# SCH_Adamjames_2023-03-12.net
KiCad netlist of a schematic drawn in EasyEDA
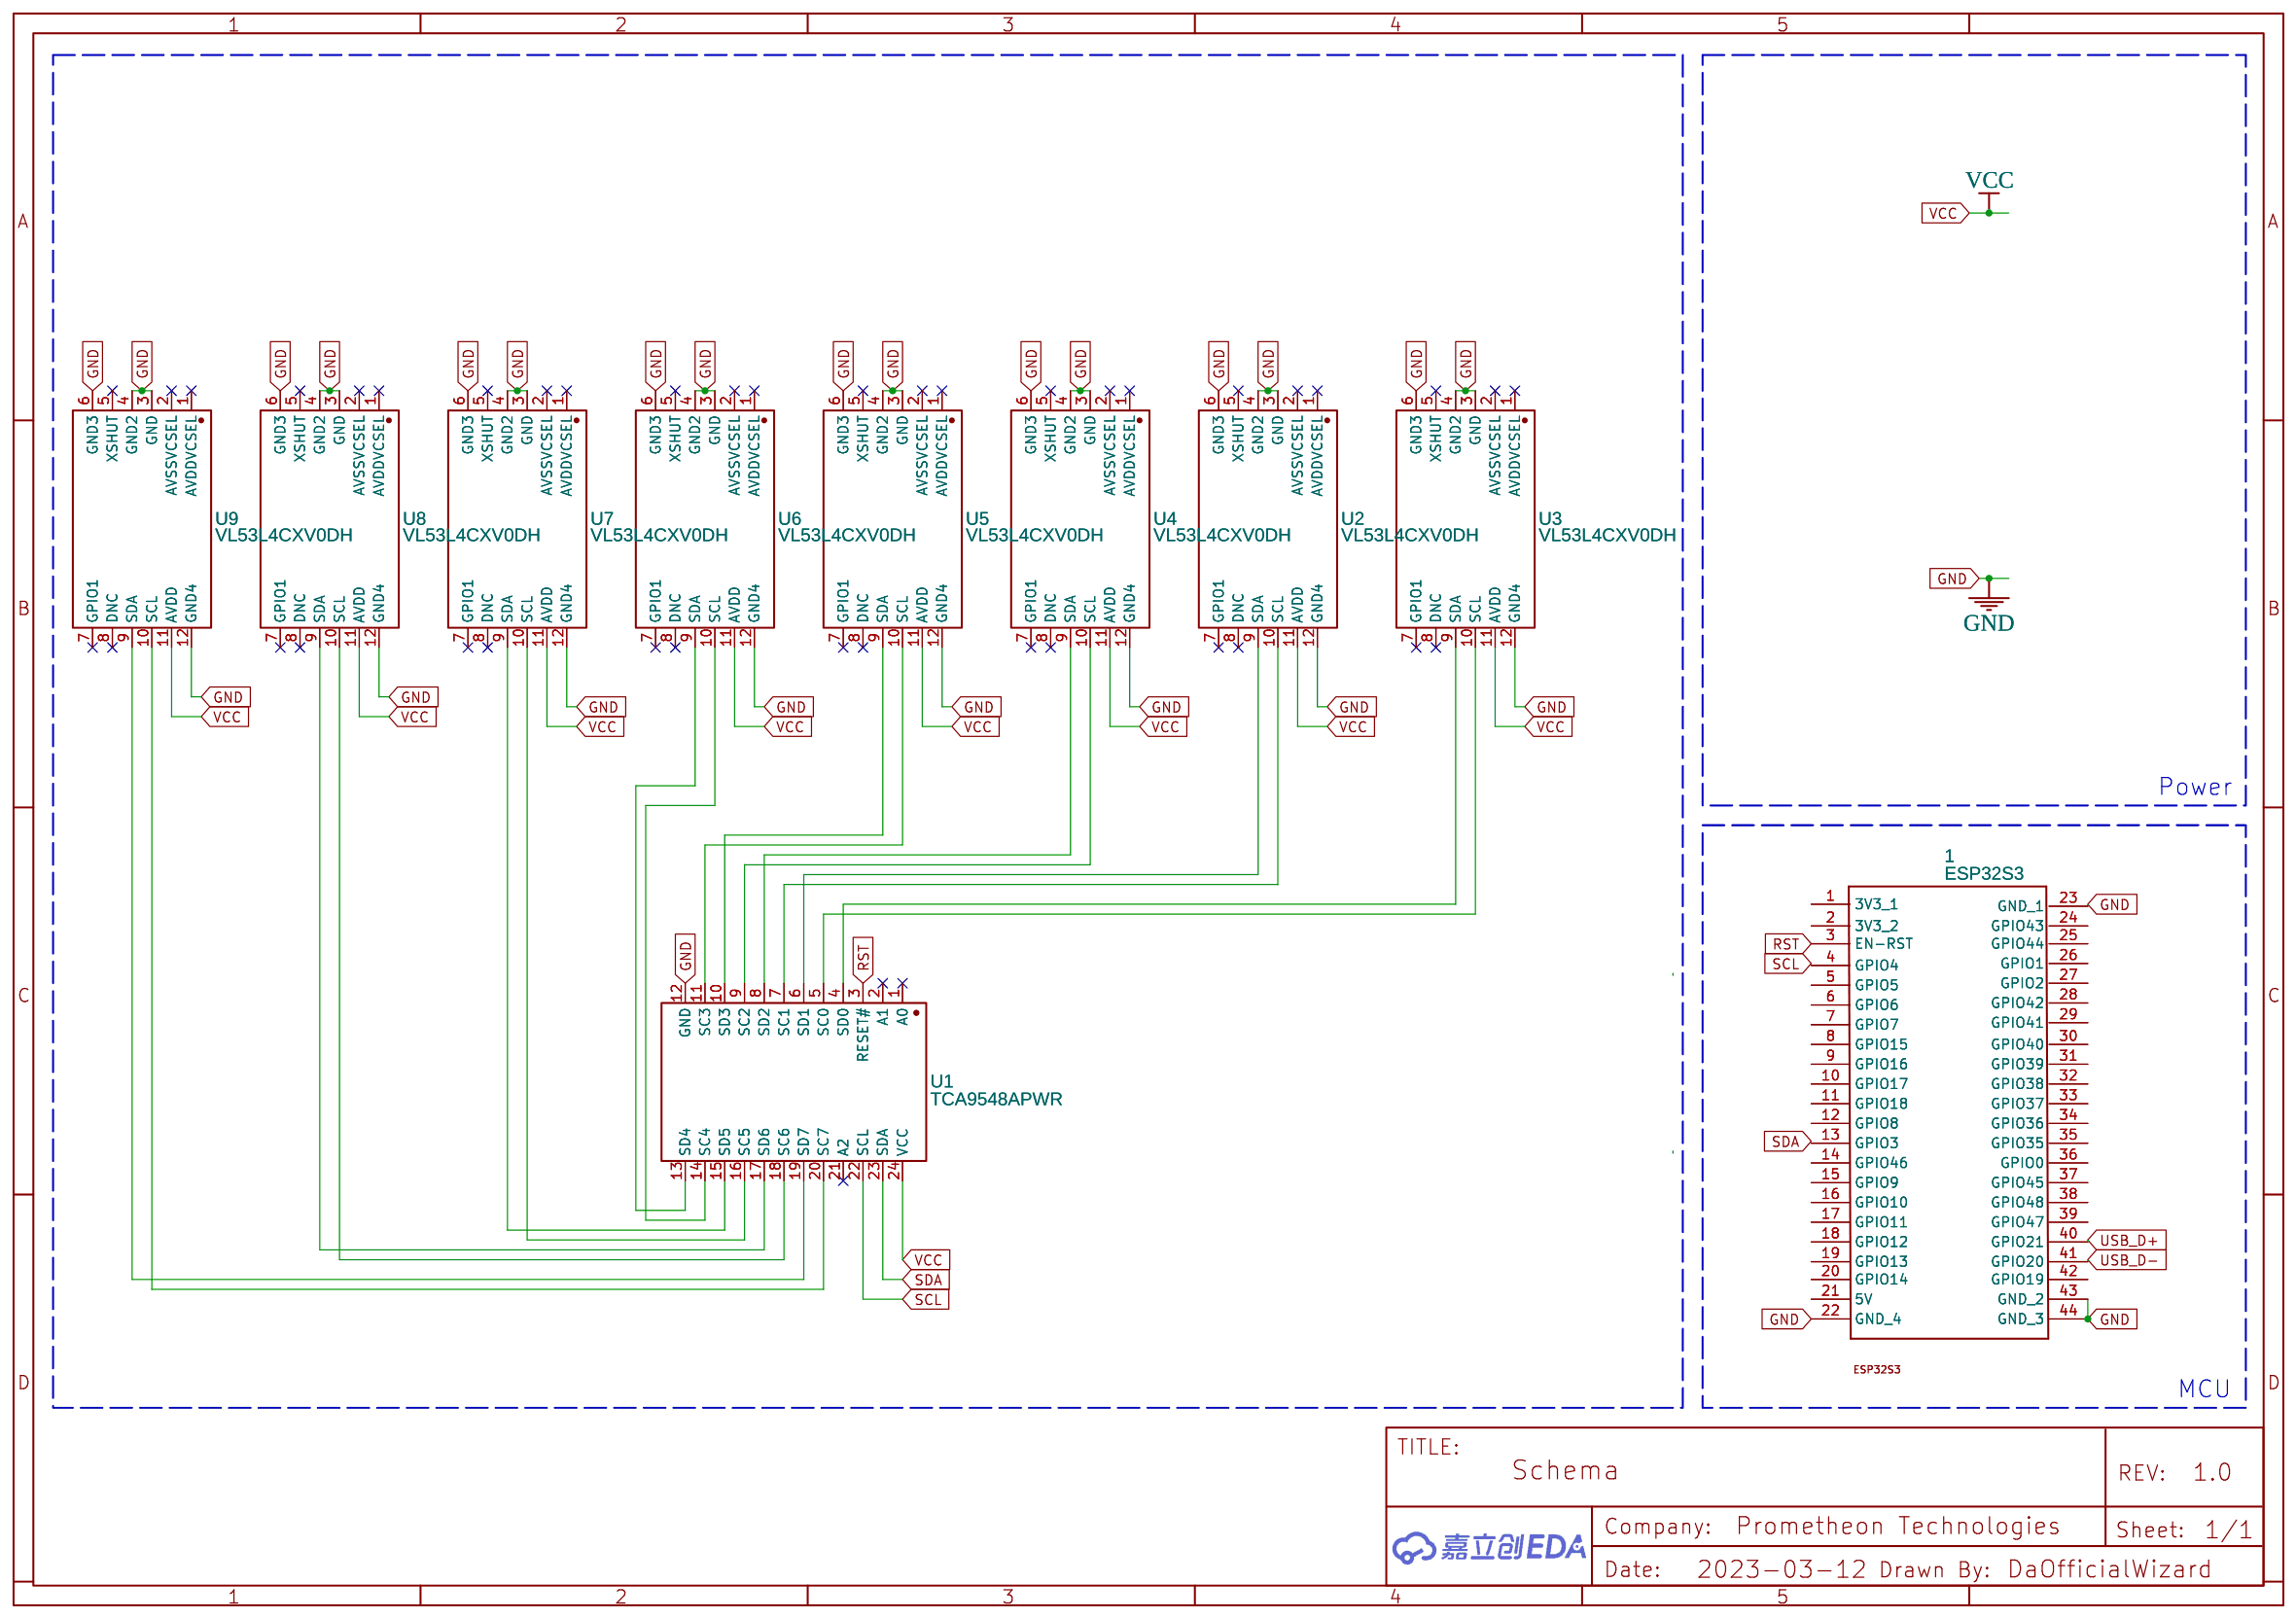
[diagram p0: schematic sheet]

(export (version "E")
  (design (tool "Eeschema 10.0.6"))
  (components
    (comp (ref "1") (value "ESP32S3") (libsource (lib "") (part "ESP32S3")))
    (comp (ref "U1")
      (value "TCA9548APWR")
      (fields (field (name "BOM_Supplier Part") "C130026"))
      (libsource (lib "") (part "TCA9548APWR"))
    )
    (comp (ref "U2")
      (value "VL53L4CXV0DH")
      (fields (field (name "BOM_Manufacturer Part") "VL53L0X") (field (name "BOM_Supplier Part") "C2929940"))
      (libsource (lib "") (part "VL53L4CXV0DH"))
    )
    (comp (ref "U3")
      (value "VL53L4CXV0DH")
      (fields (field (name "BOM_Manufacturer Part") "VL53L0X") (field (name "BOM_Supplier Part") "C2929940"))
      (libsource (lib "") (part "VL53L4CXV0DH"))
    )
    (comp (ref "U4")
      (value "VL53L4CXV0DH")
      (fields (field (name "BOM_Manufacturer Part") "VL53L0X") (field (name "BOM_Supplier Part") "C2929940"))
      (libsource (lib "") (part "VL53L4CXV0DH"))
    )
    (comp (ref "U5")
      (value "VL53L4CXV0DH")
      (fields (field (name "BOM_Manufacturer Part") "VL53L0X") (field (name "BOM_Supplier Part") "C2929940"))
      (libsource (lib "") (part "VL53L4CXV0DH"))
    )
    (comp (ref "U6")
      (value "VL53L4CXV0DH")
      (fields (field (name "BOM_Manufacturer Part") "VL53L0X") (field (name "BOM_Supplier Part") "C2929940"))
      (libsource (lib "") (part "VL53L4CXV0DH"))
    )
    (comp (ref "U7")
      (value "VL53L4CXV0DH")
      (fields (field (name "BOM_Manufacturer Part") "VL53L0X") (field (name "BOM_Supplier Part") "C2929940"))
      (libsource (lib "") (part "VL53L4CXV0DH"))
    )
    (comp (ref "U8")
      (value "VL53L4CXV0DH")
      (fields (field (name "BOM_Manufacturer Part") "VL53L0X") (field (name "BOM_Supplier Part") "C2929940"))
      (libsource (lib "") (part "VL53L4CXV0DH"))
    )
    (comp (ref "U9")
      (value "VL53L4CXV0DH")
      (fields (field (name "BOM_Manufacturer Part") "VL53L0X") (field (name "BOM_Supplier Part") "C2929940"))
      (libsource (lib "") (part "VL53L4CXV0DH"))
    )
  )
  (nets
    (net (code "1") (name "GND") (class "Default")
      (node (ref "1") (pin "22") (pinfunction "GND_4_22") (pintype "passive"))
      (node (ref "1") (pin "23") (pinfunction "GND_1_23") (pintype "passive"))
      (node (ref "1") (pin "43") (pinfunction "GND_2_43") (pintype "passive"))
      (node (ref "1") (pin "44") (pinfunction "GND_3_44") (pintype "passive"))
      (node (ref "U1") (pin "12") (pinfunction "GND_12") (pintype "unspecified"))
      (node (ref "U2") (pin "12") (pinfunction "GND4_12") (pintype "unspecified"))
      (node (ref "U2") (pin "3") (pinfunction "GND_3") (pintype "unspecified"))
      (node (ref "U2") (pin "4") (pinfunction "GND2_4") (pintype "unspecified"))
      (node (ref "U2") (pin "6") (pinfunction "GND3_6") (pintype "unspecified"))
      (node (ref "U3") (pin "12") (pinfunction "GND4_12") (pintype "unspecified"))
      (node (ref "U3") (pin "3") (pinfunction "GND_3") (pintype "unspecified"))
      (node (ref "U3") (pin "4") (pinfunction "GND2_4") (pintype "unspecified"))
      (node (ref "U3") (pin "6") (pinfunction "GND3_6") (pintype "unspecified"))
      (node (ref "U4") (pin "12") (pinfunction "GND4_12") (pintype "unspecified"))
      (node (ref "U4") (pin "3") (pinfunction "GND_3") (pintype "unspecified"))
      (node (ref "U4") (pin "4") (pinfunction "GND2_4") (pintype "unspecified"))
      (node (ref "U4") (pin "6") (pinfunction "GND3_6") (pintype "unspecified"))
      (node (ref "U5") (pin "12") (pinfunction "GND4_12") (pintype "unspecified"))
      (node (ref "U5") (pin "3") (pinfunction "GND_3") (pintype "unspecified"))
      (node (ref "U5") (pin "4") (pinfunction "GND2_4") (pintype "unspecified"))
      (node (ref "U5") (pin "6") (pinfunction "GND3_6") (pintype "unspecified"))
      (node (ref "U6") (pin "12") (pinfunction "GND4_12") (pintype "unspecified"))
      (node (ref "U6") (pin "3") (pinfunction "GND_3") (pintype "unspecified"))
      (node (ref "U6") (pin "4") (pinfunction "GND2_4") (pintype "unspecified"))
      (node (ref "U6") (pin "6") (pinfunction "GND3_6") (pintype "unspecified"))
      (node (ref "U7") (pin "12") (pinfunction "GND4_12") (pintype "unspecified"))
      (node (ref "U7") (pin "3") (pinfunction "GND_3") (pintype "unspecified"))
      (node (ref "U7") (pin "4") (pinfunction "GND2_4") (pintype "unspecified"))
      (node (ref "U7") (pin "6") (pinfunction "GND3_6") (pintype "unspecified"))
      (node (ref "U8") (pin "12") (pinfunction "GND4_12") (pintype "unspecified"))
      (node (ref "U8") (pin "3") (pinfunction "GND_3") (pintype "unspecified"))
      (node (ref "U8") (pin "4") (pinfunction "GND2_4") (pintype "unspecified"))
      (node (ref "U8") (pin "6") (pinfunction "GND3_6") (pintype "unspecified"))
      (node (ref "U9") (pin "12") (pinfunction "GND4_12") (pintype "unspecified"))
      (node (ref "U9") (pin "3") (pinfunction "GND_3") (pintype "unspecified"))
      (node (ref "U9") (pin "4") (pinfunction "GND2_4") (pintype "unspecified"))
      (node (ref "U9") (pin "6") (pinfunction "GND3_6") (pintype "unspecified"))
    )
    (net (code "2") (name "Net-(U1-SC0)") (class "Default")
      (node (ref "U1") (pin "5") (pinfunction "SC0_5") (pintype "unspecified"))
      (node (ref "U3") (pin "10") (pinfunction "SCL_10") (pintype "unspecified"))
    )
    (net (code "3") (name "Net-(U1-SC1)") (class "Default")
      (node (ref "U1") (pin "7") (pinfunction "SC1_7") (pintype "unspecified"))
      (node (ref "U2") (pin "10") (pinfunction "SCL_10") (pintype "unspecified"))
    )
    (net (code "4") (name "Net-(U1-SC2)") (class "Default")
      (node (ref "U1") (pin "9") (pinfunction "SC2_9") (pintype "unspecified"))
      (node (ref "U4") (pin "10") (pinfunction "SCL_10") (pintype "unspecified"))
    )
    (net (code "5") (name "Net-(U1-SC3)") (class "Default")
      (node (ref "U1") (pin "11") (pinfunction "SC3_11") (pintype "unspecified"))
      (node (ref "U5") (pin "10") (pinfunction "SCL_10") (pintype "unspecified"))
    )
    (net (code "6") (name "Net-(U1-SC4)") (class "Default")
      (node (ref "U1") (pin "14") (pinfunction "SC4_14") (pintype "unspecified"))
      (node (ref "U6") (pin "10") (pinfunction "SCL_10") (pintype "unspecified"))
    )
    (net (code "7") (name "Net-(U1-SC5)") (class "Default")
      (node (ref "U1") (pin "16") (pinfunction "SC5_16") (pintype "unspecified"))
      (node (ref "U7") (pin "10") (pinfunction "SCL_10") (pintype "unspecified"))
    )
    (net (code "8") (name "Net-(U1-SC6)") (class "Default")
      (node (ref "U1") (pin "18") (pinfunction "SC6_18") (pintype "unspecified"))
      (node (ref "U8") (pin "10") (pinfunction "SCL_10") (pintype "unspecified"))
    )
    (net (code "9") (name "Net-(U1-SC7)") (class "Default")
      (node (ref "U1") (pin "20") (pinfunction "SC7_20") (pintype "unspecified"))
      (node (ref "U9") (pin "10") (pinfunction "SCL_10") (pintype "unspecified"))
    )
    (net (code "10") (name "Net-(U1-SD0)") (class "Default")
      (node (ref "U1") (pin "4") (pinfunction "SD0_4") (pintype "unspecified"))
      (node (ref "U3") (pin "9") (pinfunction "SDA_9") (pintype "unspecified"))
    )
    (net (code "11") (name "Net-(U1-SD1)") (class "Default")
      (node (ref "U1") (pin "6") (pinfunction "SD1_6") (pintype "unspecified"))
      (node (ref "U2") (pin "9") (pinfunction "SDA_9") (pintype "unspecified"))
    )
    (net (code "12") (name "Net-(U1-SD2)") (class "Default")
      (node (ref "U1") (pin "8") (pinfunction "SD2_8") (pintype "unspecified"))
      (node (ref "U4") (pin "9") (pinfunction "SDA_9") (pintype "unspecified"))
    )
    (net (code "13") (name "Net-(U1-SD3)") (class "Default")
      (node (ref "U1") (pin "10") (pinfunction "SD3_10") (pintype "unspecified"))
      (node (ref "U5") (pin "9") (pinfunction "SDA_9") (pintype "unspecified"))
    )
    (net (code "14") (name "Net-(U1-SD4)") (class "Default")
      (node (ref "U1") (pin "13") (pinfunction "SD4_13") (pintype "unspecified"))
      (node (ref "U6") (pin "9") (pinfunction "SDA_9") (pintype "unspecified"))
    )
    (net (code "15") (name "Net-(U1-SD5)") (class "Default")
      (node (ref "U1") (pin "15") (pinfunction "SD5_15") (pintype "unspecified"))
      (node (ref "U7") (pin "9") (pinfunction "SDA_9") (pintype "unspecified"))
    )
    (net (code "16") (name "Net-(U1-SD6)") (class "Default")
      (node (ref "U1") (pin "17") (pinfunction "SD6_17") (pintype "unspecified"))
      (node (ref "U8") (pin "9") (pinfunction "SDA_9") (pintype "unspecified"))
    )
    (net (code "17") (name "Net-(U1-SD7)") (class "Default")
      (node (ref "U1") (pin "19") (pinfunction "SD7_19") (pintype "unspecified"))
      (node (ref "U9") (pin "9") (pinfunction "SDA_9") (pintype "unspecified"))
    )
    (net (code "18") (name "RST") (class "Default")
      (node (ref "1") (pin "3") (pinfunction "EN-RST_3") (pintype "bidirectional"))
      (node (ref "U1") (pin "3") (pinfunction "RESET#_3") (pintype "unspecified"))
    )
    (net (code "19") (name "SCL") (class "Default")
      (node (ref "U1") (pin "22") (pinfunction "SCL_22") (pintype "unspecified"))
    )
    (net (code "20") (name "SDA") (class "Default")
      (node (ref "U1") (pin "23") (pinfunction "SDA_23") (pintype "unspecified"))
    )
    (net (code "21") (name "USB_D+") (class "Default")
      (node (ref "1") (pin "40") (pinfunction "GPIO21_40") (pintype "bidirectional"))
    )
    (net (code "22") (name "USB_D-") (class "Default")
      (node (ref "1") (pin "41") (pinfunction "GPIO20_41") (pintype "bidirectional"))
    )
    (net (code "23") (name "VCC") (class "Default")
      (node (ref "U1") (pin "24") (pinfunction "VCC_24") (pintype "unspecified"))
      (node (ref "U2") (pin "11") (pinfunction "AVDD_11") (pintype "unspecified"))
      (node (ref "U3") (pin "11") (pinfunction "AVDD_11") (pintype "unspecified"))
      (node (ref "U4") (pin "11") (pinfunction "AVDD_11") (pintype "unspecified"))
      (node (ref "U5") (pin "11") (pinfunction "AVDD_11") (pintype "unspecified"))
      (node (ref "U6") (pin "11") (pinfunction "AVDD_11") (pintype "unspecified"))
      (node (ref "U7") (pin "11") (pinfunction "AVDD_11") (pintype "unspecified"))
      (node (ref "U8") (pin "11") (pinfunction "AVDD_11") (pintype "unspecified"))
      (node (ref "U9") (pin "11") (pinfunction "AVDD_11") (pintype "unspecified"))
    )
    (net (code "24") (name "unconnected-(1-3V3_1-Pad1)") (class "Default")
      (node (ref "1") (pin "1") (pinfunction "3V3_1_1") (pintype "passive"))
    )
    (net (code "25") (name "unconnected-(1-3V3_2-Pad2)") (class "Default")
      (node (ref "1") (pin "2") (pinfunction "3V3_2_2") (pintype "passive"))
    )
    (net (code "26") (name "unconnected-(1-5V-Pad21)") (class "Default")
      (node (ref "1") (pin "21") (pinfunction "5V_21") (pintype "passive"))
    )
    (net (code "27") (name "unconnected-(1-GPIO0-Pad36)") (class "Default")
      (node (ref "1") (pin "36") (pinfunction "GPIO0_36") (pintype "bidirectional"))
    )
    (net (code "28") (name "unconnected-(1-GPIO1-Pad26)") (class "Default")
      (node (ref "1") (pin "26") (pinfunction "GPIO1_26") (pintype "bidirectional"))
    )
    (net (code "29") (name "unconnected-(1-GPIO2-Pad27)") (class "Default")
      (node (ref "1") (pin "27") (pinfunction "GPIO2_27") (pintype "bidirectional"))
    )
    (net (code "30") (name "unconnected-(1-GPIO3-Pad13)") (class "Default")
      (node (ref "1") (pin "13") (pinfunction "GPIO3_13") (pintype "bidirectional"))
    )
    (net (code "31") (name "unconnected-(1-GPIO4-Pad4)") (class "Default")
      (node (ref "1") (pin "4") (pinfunction "GPIO4_4") (pintype "bidirectional"))
    )
    (net (code "32") (name "unconnected-(1-GPIO5-Pad5)") (class "Default")
      (node (ref "1") (pin "5") (pinfunction "GPIO5_5") (pintype "bidirectional"))
    )
    (net (code "33") (name "unconnected-(1-GPIO6-Pad6)") (class "Default")
      (node (ref "1") (pin "6") (pinfunction "GPIO6_6") (pintype "bidirectional"))
    )
    (net (code "34") (name "unconnected-(1-GPIO7-Pad7)") (class "Default")
      (node (ref "1") (pin "7") (pinfunction "GPIO7_7") (pintype "bidirectional"))
    )
    (net (code "35") (name "unconnected-(1-GPIO8-Pad12)") (class "Default")
      (node (ref "1") (pin "12") (pinfunction "GPIO8_12") (pintype "bidirectional"))
    )
    (net (code "36") (name "unconnected-(1-GPIO9-Pad15)") (class "Default")
      (node (ref "1") (pin "15") (pinfunction "GPIO9_15") (pintype "bidirectional"))
    )
    (net (code "37") (name "unconnected-(1-GPIO10-Pad16)") (class "Default")
      (node (ref "1") (pin "16") (pinfunction "GPIO10_16") (pintype "bidirectional"))
    )
    (net (code "38") (name "unconnected-(1-GPIO11-Pad17)") (class "Default")
      (node (ref "1") (pin "17") (pinfunction "GPIO11_17") (pintype "bidirectional"))
    )
    (net (code "39") (name "unconnected-(1-GPIO12-Pad18)") (class "Default")
      (node (ref "1") (pin "18") (pinfunction "GPIO12_18") (pintype "bidirectional"))
    )
    (net (code "40") (name "unconnected-(1-GPIO13-Pad19)") (class "Default")
      (node (ref "1") (pin "19") (pinfunction "GPIO13_19") (pintype "bidirectional"))
    )
    (net (code "41") (name "unconnected-(1-GPIO14-Pad20)") (class "Default")
      (node (ref "1") (pin "20") (pinfunction "GPIO14_20") (pintype "bidirectional"))
    )
    (net (code "42") (name "unconnected-(1-GPIO15-Pad8)") (class "Default")
      (node (ref "1") (pin "8") (pinfunction "GPIO15_8") (pintype "bidirectional"))
    )
    (net (code "43") (name "unconnected-(1-GPIO16-Pad9)") (class "Default")
      (node (ref "1") (pin "9") (pinfunction "GPIO16_9") (pintype "bidirectional"))
    )
    (net (code "44") (name "unconnected-(1-GPIO17-Pad10)") (class "Default")
      (node (ref "1") (pin "10") (pinfunction "GPIO17_10") (pintype "bidirectional"))
    )
    (net (code "45") (name "unconnected-(1-GPIO18-Pad11)") (class "Default")
      (node (ref "1") (pin "11") (pinfunction "GPIO18_11") (pintype "bidirectional"))
    )
    (net (code "46") (name "unconnected-(1-GPIO19-Pad42)") (class "Default")
      (node (ref "1") (pin "42") (pinfunction "GPIO19_42") (pintype "bidirectional"))
    )
    (net (code "47") (name "unconnected-(1-GPIO35-Pad35)") (class "Default")
      (node (ref "1") (pin "35") (pinfunction "GPIO35_35") (pintype "bidirectional"))
    )
    (net (code "48") (name "unconnected-(1-GPIO36-Pad34)") (class "Default")
      (node (ref "1") (pin "34") (pinfunction "GPIO36_34") (pintype "bidirectional"))
    )
    (net (code "49") (name "unconnected-(1-GPIO37-Pad33)") (class "Default")
      (node (ref "1") (pin "33") (pinfunction "GPIO37_33") (pintype "bidirectional"))
    )
    (net (code "50") (name "unconnected-(1-GPIO38-Pad32)") (class "Default")
      (node (ref "1") (pin "32") (pinfunction "GPIO38_32") (pintype "bidirectional"))
    )
    (net (code "51") (name "unconnected-(1-GPIO39-Pad31)") (class "Default")
      (node (ref "1") (pin "31") (pinfunction "GPIO39_31") (pintype "bidirectional"))
    )
    (net (code "52") (name "unconnected-(1-GPIO40-Pad30)") (class "Default")
      (node (ref "1") (pin "30") (pinfunction "GPIO40_30") (pintype "bidirectional"))
    )
    (net (code "53") (name "unconnected-(1-GPIO41-Pad29)") (class "Default")
      (node (ref "1") (pin "29") (pinfunction "GPIO41_29") (pintype "bidirectional"))
    )
    (net (code "54") (name "unconnected-(1-GPIO42-Pad28)") (class "Default")
      (node (ref "1") (pin "28") (pinfunction "GPIO42_28") (pintype "bidirectional"))
    )
    (net (code "55") (name "unconnected-(1-GPIO43-Pad24)") (class "Default")
      (node (ref "1") (pin "24") (pinfunction "GPIO43_24") (pintype "bidirectional"))
    )
    (net (code "56") (name "unconnected-(1-GPIO44-Pad25)") (class "Default")
      (node (ref "1") (pin "25") (pinfunction "GPIO44_25") (pintype "bidirectional"))
    )
    (net (code "57") (name "unconnected-(1-GPIO45-Pad37)") (class "Default")
      (node (ref "1") (pin "37") (pinfunction "GPIO45_37") (pintype "bidirectional"))
    )
    (net (code "58") (name "unconnected-(1-GPIO46-Pad14)") (class "Default")
      (node (ref "1") (pin "14") (pinfunction "GPIO46_14") (pintype "bidirectional"))
    )
    (net (code "59") (name "unconnected-(1-GPIO47-Pad39)") (class "Default")
      (node (ref "1") (pin "39") (pinfunction "GPIO47_39") (pintype "bidirectional"))
    )
    (net (code "60") (name "unconnected-(1-GPIO48-Pad38)") (class "Default")
      (node (ref "1") (pin "38") (pinfunction "GPIO48_38") (pintype "bidirectional"))
    )
    (net (code "61") (name "unconnected-(U1-A0-Pad1)") (class "Default")
      (node (ref "U1") (pin "1") (pinfunction "A0_1") (pintype "unspecified+no_connect"))
    )
    (net (code "62") (name "unconnected-(U1-A1-Pad2)") (class "Default")
      (node (ref "U1") (pin "2") (pinfunction "A1_2") (pintype "unspecified+no_connect"))
    )
    (net (code "63") (name "unconnected-(U1-A2-Pad21)") (class "Default")
      (node (ref "U1") (pin "21") (pinfunction "A2_21") (pintype "unspecified+no_connect"))
    )
    (net (code "64") (name "unconnected-(U2-AVDDVCSEL-Pad1)") (class "Default")
      (node (ref "U2") (pin "1") (pinfunction "AVDDVCSEL_1") (pintype "unspecified+no_connect"))
    )
    (net (code "65") (name "unconnected-(U2-AVSSVCSEL-Pad2)") (class "Default")
      (node (ref "U2") (pin "2") (pinfunction "AVSSVCSEL_2") (pintype "unspecified+no_connect"))
    )
    (net (code "66") (name "unconnected-(U2-DNC-Pad8)") (class "Default")
      (node (ref "U2") (pin "8") (pinfunction "DNC_8") (pintype "unspecified+no_connect"))
    )
    (net (code "67") (name "unconnected-(U2-GPIO1-Pad7)") (class "Default")
      (node (ref "U2") (pin "7") (pinfunction "GPIO1_7") (pintype "unspecified+no_connect"))
    )
    (net (code "68") (name "unconnected-(U2-XSHUT-Pad5)") (class "Default")
      (node (ref "U2") (pin "5") (pinfunction "XSHUT_5") (pintype "unspecified+no_connect"))
    )
    (net (code "69") (name "unconnected-(U3-AVDDVCSEL-Pad1)") (class "Default")
      (node (ref "U3") (pin "1") (pinfunction "AVDDVCSEL_1") (pintype "unspecified+no_connect"))
    )
    (net (code "70") (name "unconnected-(U3-AVSSVCSEL-Pad2)") (class "Default")
      (node (ref "U3") (pin "2") (pinfunction "AVSSVCSEL_2") (pintype "unspecified+no_connect"))
    )
    (net (code "71") (name "unconnected-(U3-DNC-Pad8)") (class "Default")
      (node (ref "U3") (pin "8") (pinfunction "DNC_8") (pintype "unspecified+no_connect"))
    )
    (net (code "72") (name "unconnected-(U3-GPIO1-Pad7)") (class "Default")
      (node (ref "U3") (pin "7") (pinfunction "GPIO1_7") (pintype "unspecified+no_connect"))
    )
    (net (code "73") (name "unconnected-(U3-XSHUT-Pad5)") (class "Default")
      (node (ref "U3") (pin "5") (pinfunction "XSHUT_5") (pintype "unspecified+no_connect"))
    )
    (net (code "74") (name "unconnected-(U4-AVDDVCSEL-Pad1)") (class "Default")
      (node (ref "U4") (pin "1") (pinfunction "AVDDVCSEL_1") (pintype "unspecified+no_connect"))
    )
    (net (code "75") (name "unconnected-(U4-AVSSVCSEL-Pad2)") (class "Default")
      (node (ref "U4") (pin "2") (pinfunction "AVSSVCSEL_2") (pintype "unspecified+no_connect"))
    )
    (net (code "76") (name "unconnected-(U4-DNC-Pad8)") (class "Default")
      (node (ref "U4") (pin "8") (pinfunction "DNC_8") (pintype "unspecified+no_connect"))
    )
    (net (code "77") (name "unconnected-(U4-GPIO1-Pad7)") (class "Default")
      (node (ref "U4") (pin "7") (pinfunction "GPIO1_7") (pintype "unspecified+no_connect"))
    )
    (net (code "78") (name "unconnected-(U4-XSHUT-Pad5)") (class "Default")
      (node (ref "U4") (pin "5") (pinfunction "XSHUT_5") (pintype "unspecified+no_connect"))
    )
    (net (code "79") (name "unconnected-(U5-AVDDVCSEL-Pad1)") (class "Default")
      (node (ref "U5") (pin "1") (pinfunction "AVDDVCSEL_1") (pintype "unspecified+no_connect"))
    )
    (net (code "80") (name "unconnected-(U5-AVSSVCSEL-Pad2)") (class "Default")
      (node (ref "U5") (pin "2") (pinfunction "AVSSVCSEL_2") (pintype "unspecified+no_connect"))
    )
    (net (code "81") (name "unconnected-(U5-DNC-Pad8)") (class "Default")
      (node (ref "U5") (pin "8") (pinfunction "DNC_8") (pintype "unspecified+no_connect"))
    )
    (net (code "82") (name "unconnected-(U5-GPIO1-Pad7)") (class "Default")
      (node (ref "U5") (pin "7") (pinfunction "GPIO1_7") (pintype "unspecified+no_connect"))
    )
    (net (code "83") (name "unconnected-(U5-XSHUT-Pad5)") (class "Default")
      (node (ref "U5") (pin "5") (pinfunction "XSHUT_5") (pintype "unspecified+no_connect"))
    )
    (net (code "84") (name "unconnected-(U6-AVDDVCSEL-Pad1)") (class "Default")
      (node (ref "U6") (pin "1") (pinfunction "AVDDVCSEL_1") (pintype "unspecified+no_connect"))
    )
    (net (code "85") (name "unconnected-(U6-AVSSVCSEL-Pad2)") (class "Default")
      (node (ref "U6") (pin "2") (pinfunction "AVSSVCSEL_2") (pintype "unspecified+no_connect"))
    )
    (net (code "86") (name "unconnected-(U6-DNC-Pad8)") (class "Default")
      (node (ref "U6") (pin "8") (pinfunction "DNC_8") (pintype "unspecified+no_connect"))
    )
    (net (code "87") (name "unconnected-(U6-GPIO1-Pad7)") (class "Default")
      (node (ref "U6") (pin "7") (pinfunction "GPIO1_7") (pintype "unspecified+no_connect"))
    )
    (net (code "88") (name "unconnected-(U6-XSHUT-Pad5)") (class "Default")
      (node (ref "U6") (pin "5") (pinfunction "XSHUT_5") (pintype "unspecified+no_connect"))
    )
    (net (code "89") (name "unconnected-(U7-AVDDVCSEL-Pad1)") (class "Default")
      (node (ref "U7") (pin "1") (pinfunction "AVDDVCSEL_1") (pintype "unspecified+no_connect"))
    )
    (net (code "90") (name "unconnected-(U7-AVSSVCSEL-Pad2)") (class "Default")
      (node (ref "U7") (pin "2") (pinfunction "AVSSVCSEL_2") (pintype "unspecified+no_connect"))
    )
    (net (code "91") (name "unconnected-(U7-DNC-Pad8)") (class "Default")
      (node (ref "U7") (pin "8") (pinfunction "DNC_8") (pintype "unspecified+no_connect"))
    )
    (net (code "92") (name "unconnected-(U7-GPIO1-Pad7)") (class "Default")
      (node (ref "U7") (pin "7") (pinfunction "GPIO1_7") (pintype "unspecified+no_connect"))
    )
    (net (code "93") (name "unconnected-(U7-XSHUT-Pad5)") (class "Default")
      (node (ref "U7") (pin "5") (pinfunction "XSHUT_5") (pintype "unspecified+no_connect"))
    )
    (net (code "94") (name "unconnected-(U8-AVDDVCSEL-Pad1)") (class "Default")
      (node (ref "U8") (pin "1") (pinfunction "AVDDVCSEL_1") (pintype "unspecified+no_connect"))
    )
    (net (code "95") (name "unconnected-(U8-AVSSVCSEL-Pad2)") (class "Default")
      (node (ref "U8") (pin "2") (pinfunction "AVSSVCSEL_2") (pintype "unspecified+no_connect"))
    )
    (net (code "96") (name "unconnected-(U8-DNC-Pad8)") (class "Default")
      (node (ref "U8") (pin "8") (pinfunction "DNC_8") (pintype "unspecified+no_connect"))
    )
    (net (code "97") (name "unconnected-(U8-GPIO1-Pad7)") (class "Default")
      (node (ref "U8") (pin "7") (pinfunction "GPIO1_7") (pintype "unspecified+no_connect"))
    )
    (net (code "98") (name "unconnected-(U8-XSHUT-Pad5)") (class "Default")
      (node (ref "U8") (pin "5") (pinfunction "XSHUT_5") (pintype "unspecified+no_connect"))
    )
    (net (code "99") (name "unconnected-(U9-AVDDVCSEL-Pad1)") (class "Default")
      (node (ref "U9") (pin "1") (pinfunction "AVDDVCSEL_1") (pintype "unspecified+no_connect"))
    )
    (net (code "100") (name "unconnected-(U9-AVSSVCSEL-Pad2)") (class "Default")
      (node (ref "U9") (pin "2") (pinfunction "AVSSVCSEL_2") (pintype "unspecified+no_connect"))
    )
    (net (code "101") (name "unconnected-(U9-DNC-Pad8)") (class "Default")
      (node (ref "U9") (pin "8") (pinfunction "DNC_8") (pintype "unspecified+no_connect"))
    )
    (net (code "102") (name "unconnected-(U9-GPIO1-Pad7)") (class "Default")
      (node (ref "U9") (pin "7") (pinfunction "GPIO1_7") (pintype "unspecified+no_connect"))
    )
    (net (code "103") (name "unconnected-(U9-XSHUT-Pad5)") (class "Default")
      (node (ref "U9") (pin "5") (pinfunction "XSHUT_5") (pintype "unspecified+no_connect"))
    )
  )
)
